# Shutdown_2019_v1_1_Faults.net
KiCad netlist of a schematic drawn in Altium Designer
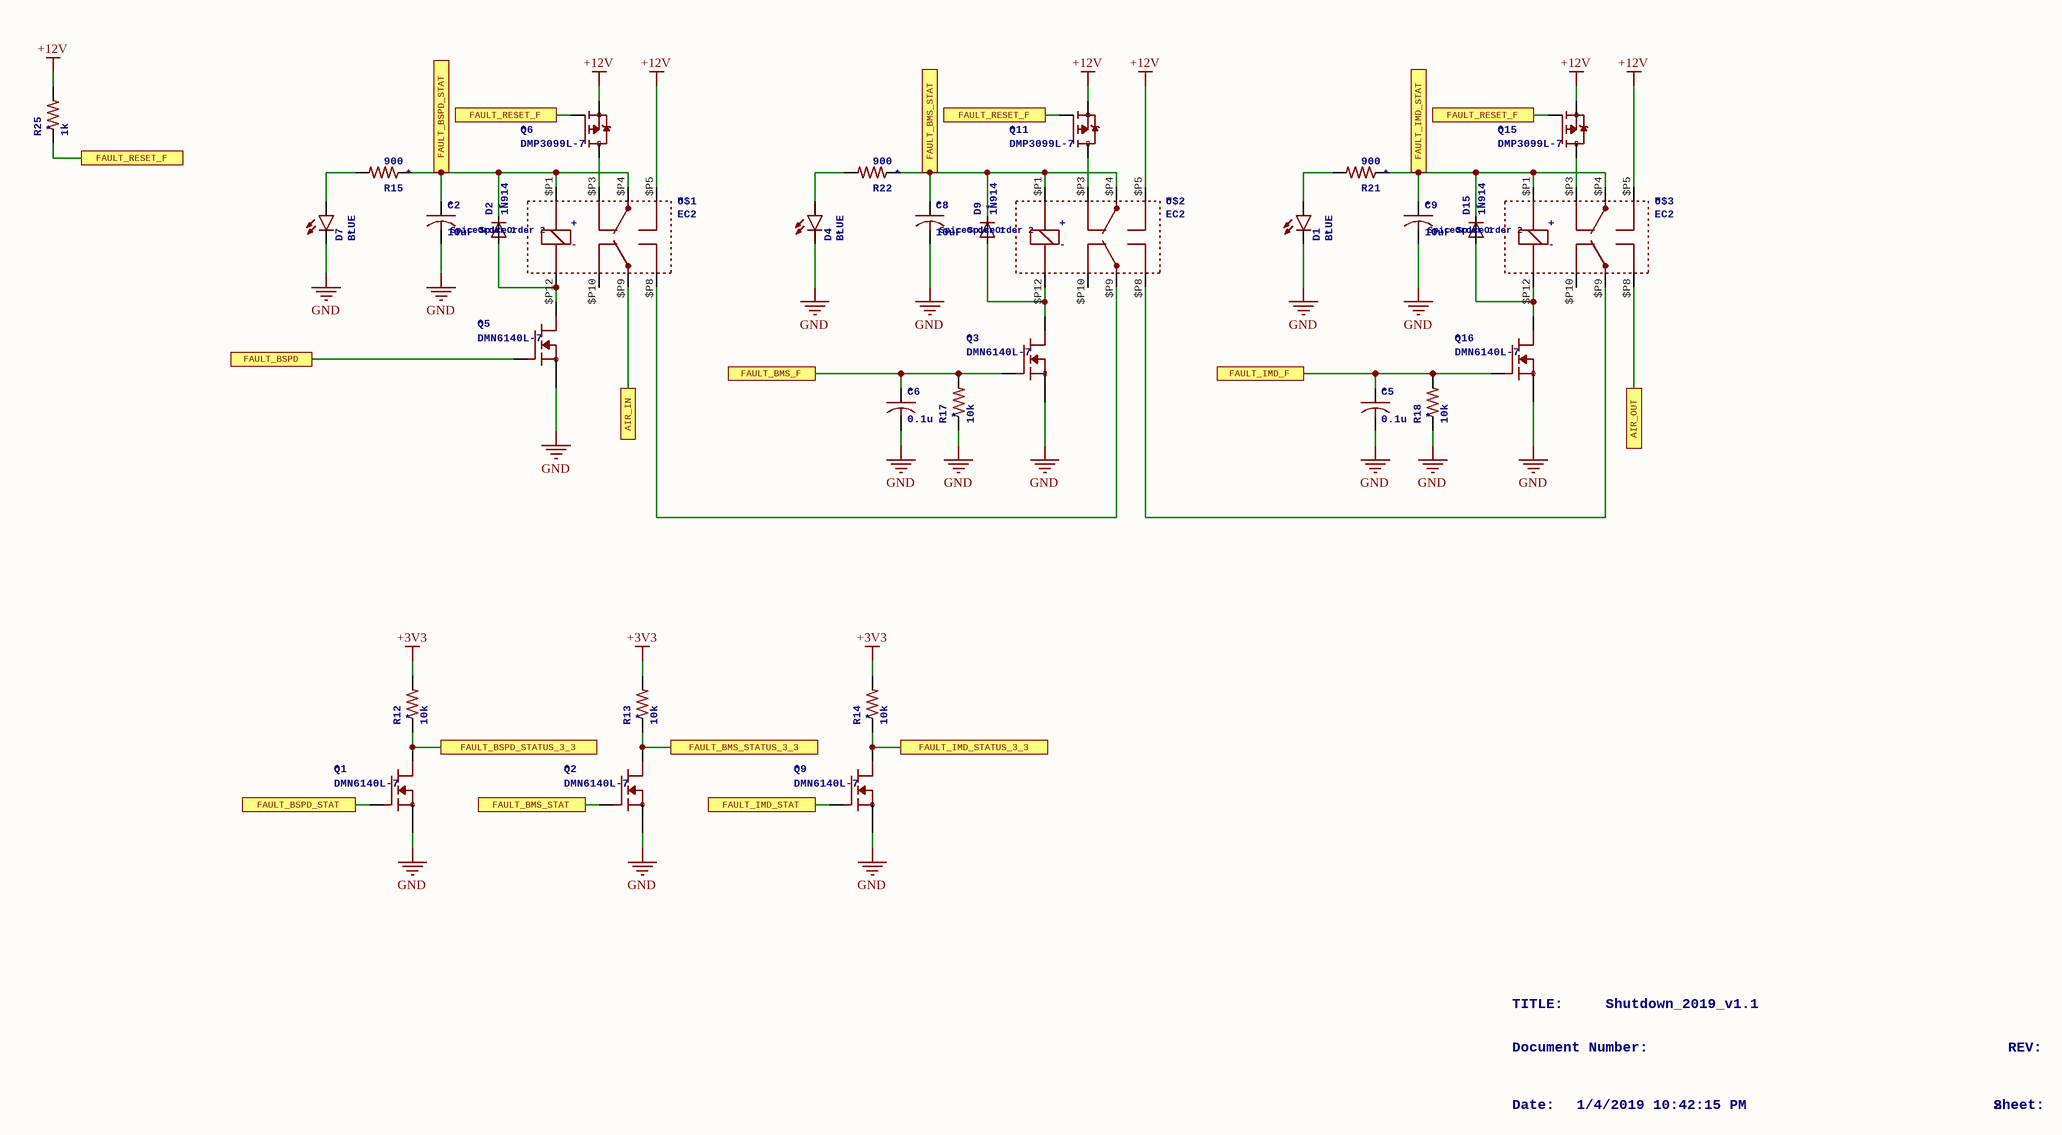
[diagram p0: Shutdown_2019_v1.1_Faults.SchDoc]

(export (version "E")
  (design (tool "Eeschema 10.0.6"))
  (components
    (comp (ref "C2")
      (value "10uF")
      (footprint "C0805")
      (description "CAPACITOR, American symbol")
      (fields (field (name "NAME") "*"))
      (libsource (lib "rcl") (part "C-USC0805"))
    )
    (comp (ref "C5")
      (value "0.1u")
      (footprint "C0603")
      (description "CAPACITOR, American symbol")
      (fields (field (name "NAME") "*"))
      (libsource (lib "resistor") (part "C-USC0603"))
    )
    (comp (ref "C6")
      (value "0.1u")
      (footprint "C0603")
      (description "CAPACITOR, American symbol")
      (fields (field (name "NAME") "*"))
      (libsource (lib "resistor") (part "C-USC0603"))
    )
    (comp (ref "C8")
      (value "10uF")
      (footprint "C0805")
      (description "CAPACITOR, American symbol")
      (fields (field (name "NAME") "*"))
      (libsource (lib "rcl") (part "C-USC0805"))
    )
    (comp (ref "C9")
      (value "10uF")
      (footprint "C0805")
      (description "CAPACITOR, American symbol")
      (fields (field (name "NAME") "*"))
      (libsource (lib "rcl") (part "C-USC0805"))
    )
    (comp (ref "D1")
      (value "BLUE")
      (footprint "LED-0603")
      (fields (field (name "NAME") "*"))
      (libsource (lib "SparkFun-LED") (part "LED-BLUE0603"))
    )
    (comp (ref "D2")
      (value "1N914")
      (footprint "SOD323-F")
      (fields
        (field (name "NAME") "*")
        (field (name "SPICEORDER1") "SpiceOrder 1")
        (field (name "SPICEORDER2") "SpiceOrder 2")
      )
      (libsource (lib "Diodes") (part "1N914"))
    )
    (comp (ref "D4")
      (value "BLUE")
      (footprint "LED-0603")
      (fields (field (name "NAME") "*"))
      (libsource (lib "SparkFun-LED") (part "LED-BLUE0603"))
    )
    (comp (ref "D7")
      (value "BLUE")
      (footprint "LED-0603")
      (fields (field (name "NAME") "*"))
      (libsource (lib "SparkFun-LED") (part "LED-BLUE0603"))
    )
    (comp (ref "D9")
      (value "1N914")
      (footprint "SOD323-F")
      (fields
        (field (name "NAME") "*")
        (field (name "SPICEORDER1") "SpiceOrder 1")
        (field (name "SPICEORDER2") "SpiceOrder 2")
      )
      (libsource (lib "Diodes") (part "1N914"))
    )
    (comp (ref "D15")
      (value "1N914")
      (footprint "SOD323-F")
      (fields
        (field (name "NAME") "*")
        (field (name "SPICEORDER1") "SpiceOrder 1")
        (field (name "SPICEORDER2") "SpiceOrder 2")
      )
      (libsource (lib "Diodes") (part "1N914"))
    )
    (comp (ref "Q1")
      (value "DMN6140L-7")
      (footprint "SOT23")
      (description "DMN6140L-7 Vgs(th) = 3V, Rds(on) = 140mOhm, Vds(max) = 60V")
      (fields (field (name "NAME") "*"))
      (libsource (lib "TRANS") (part "DMN6140L-7"))
    )
    (comp (ref "Q2")
      (value "DMN6140L-7")
      (footprint "SOT23")
      (description "DMN6140L-7 Vgs(th) = 3V, Rds(on) = 140mOhm, Vds(max) = 60V")
      (fields (field (name "NAME") "*"))
      (libsource (lib "TRANS") (part "DMN6140L-7"))
    )
    (comp (ref "Q3")
      (value "DMN6140L-7")
      (footprint "SOT23")
      (description "DMN6140L-7 Vgs(th) = 3V, Rds(on) = 140mOhm, Vds(max) = 60V")
      (fields (field (name "NAME") "*"))
      (libsource (lib "TRANS") (part "DMN6140L-7"))
    )
    (comp (ref "Q5")
      (value "DMN6140L-7")
      (footprint "SOT23")
      (description "DMN6140L-7 Vgs(th) = 3V, Rds(on) = 140mOhm, Vds(max) = 60V")
      (fields (field (name "NAME") "*"))
      (libsource (lib "TRANS") (part "DMN6140L-7"))
    )
    (comp (ref "Q6")
      (value "DMP3099L-7")
      (footprint "SOT23")
      (description "DMP3099L-7  P-Channel Vgs(th) = 2.1V, Rds(on) = 64 mohm, Vds(max) = 30V")
      (fields (field (name "NAME") "*"))
      (libsource (lib "TRANS") (part "DMP3099L-7"))
    )
    (comp (ref "Q9")
      (value "DMN6140L-7")
      (footprint "SOT23")
      (description "DMN6140L-7 Vgs(th) = 3V, Rds(on) = 140mOhm, Vds(max) = 60V")
      (fields (field (name "NAME") "*"))
      (libsource (lib "TRANS") (part "DMN6140L-7"))
    )
    (comp (ref "Q11")
      (value "DMP3099L-7")
      (footprint "SOT23")
      (description "DMP3099L-7  P-Channel Vgs(th) = 2.1V, Rds(on) = 64 mohm, Vds(max) = 30V")
      (fields (field (name "NAME") "*"))
      (libsource (lib "TRANS") (part "DMP3099L-7"))
    )
    (comp (ref "Q15")
      (value "DMP3099L-7")
      (footprint "SOT23")
      (description "DMP3099L-7  P-Channel Vgs(th) = 2.1V, Rds(on) = 64 mohm, Vds(max) = 30V")
      (fields (field (name "NAME") "*"))
      (libsource (lib "TRANS") (part "DMP3099L-7"))
    )
    (comp (ref "Q16")
      (value "DMN6140L-7")
      (footprint "SOT23")
      (description "DMN6140L-7 Vgs(th) = 3V, Rds(on) = 140mOhm, Vds(max) = 60V")
      (fields (field (name "NAME") "*"))
      (libsource (lib "TRANS") (part "DMN6140L-7"))
    )
    (comp (ref "R12")
      (value "10k")
      (footprint "R0603")
      (description "RESISTOR, American symbol")
      (fields (field (name "NAME") "*"))
      (libsource (lib "resistor") (part "R-US_R0603"))
    )
    (comp (ref "R13")
      (value "10k")
      (footprint "R0603")
      (description "RESISTOR, American symbol")
      (fields (field (name "NAME") "*"))
      (libsource (lib "resistor") (part "R-US_R0603"))
    )
    (comp (ref "R14")
      (value "10k")
      (footprint "R0603")
      (description "RESISTOR, American symbol")
      (fields (field (name "NAME") "*"))
      (libsource (lib "resistor") (part "R-US_R0603"))
    )
    (comp (ref "R15")
      (value "900")
      (footprint "R0603")
      (description "RESISTOR, American symbol")
      (fields (field (name "NAME") "*"))
      (libsource (lib "resistor") (part "R-US_R0603"))
    )
    (comp (ref "R17")
      (value "10k")
      (footprint "R0603")
      (description "RESISTOR, American symbol")
      (fields (field (name "NAME") "*"))
      (libsource (lib "resistor") (part "R-US_R0603"))
    )
    (comp (ref "R18")
      (value "10k")
      (footprint "R0603")
      (description "RESISTOR, American symbol")
      (fields (field (name "NAME") "*"))
      (libsource (lib "resistor") (part "R-US_R0603"))
    )
    (comp (ref "R21")
      (value "900")
      (footprint "R0603")
      (description "RESISTOR, American symbol")
      (fields (field (name "NAME") "*"))
      (libsource (lib "resistor") (part "R-US_R0603"))
    )
    (comp (ref "R22")
      (value "900")
      (footprint "R0603")
      (description "RESISTOR, American symbol")
      (fields (field (name "NAME") "*"))
      (libsource (lib "resistor") (part "R-US_R0603"))
    )
    (comp (ref "R25")
      (value "1k")
      (footprint "R0603")
      (description "RESISTOR, American symbol")
      (fields (field (name "NAME") "*"))
      (libsource (lib "resistor") (part "R-US_R0603"))
    )
    (comp (ref "U$1")
      (value "EC2")
      (footprint "DPDT_2.54")
      (description "KEMET EC2 DPDT General Purpose 2A Relay. 12V coil voltage.Datasheet Digikey")
      (fields (field (name "NAME") "*") (field (name "+") "+") (field (name "-") "-"))
      (libsource (lib "KEMET") (part "EC2"))
    )
    (comp (ref "U$2")
      (value "EC2")
      (footprint "DPDT_2.54")
      (description "KEMET EC2 DPDT General Purpose 2A Relay. 12V coil voltage.Datasheet Digikey")
      (fields (field (name "NAME") "*") (field (name "+") "+") (field (name "-") "-"))
      (libsource (lib "KEMET") (part "EC2"))
    )
    (comp (ref "U$3")
      (value "EC2")
      (footprint "DPDT_2.54")
      (description "KEMET EC2 DPDT General Purpose 2A Relay. 12V coil voltage.Datasheet Digikey")
      (fields (field (name "NAME") "*") (field (name "+") "+") (field (name "-") "-"))
      (libsource (lib "KEMET") (part "EC2"))
    )
  )
  (nets
    (net (code "1") (name "+3V3") (class "Default")
      (node (ref "R12") (pin "2") (pinfunction "2_2") (pintype "passive"))
      (node (ref "R13") (pin "2") (pinfunction "2_2") (pintype "passive"))
      (node (ref "R14") (pin "2") (pinfunction "2_2") (pintype "passive"))
    )
    (net (code "2") (name "+12V") (class "Default")
      (node (ref "Q11") (pin "2") (pinfunction "S_2") (pintype "passive"))
      (node (ref "Q15") (pin "2") (pinfunction "S_2") (pintype "passive"))
      (node (ref "Q6") (pin "2") (pinfunction "S_2") (pintype "passive"))
      (node (ref "R25") (pin "2") (pinfunction "2_2") (pintype "passive"))
      (node (ref "U$1") (pin "$P5") (pinfunction "$P5_$P5") (pintype "passive"))
      (node (ref "U$2") (pin "$P5") (pinfunction "$P5_$P5") (pintype "passive"))
      (node (ref "U$3") (pin "$P5") (pinfunction "$P5_$P5") (pintype "passive"))
    )
    (net (code "3") (name "/AIR_IN") (class "Default")
      (node (ref "U$1") (pin "$P9") (pinfunction "$P9_$P9") (pintype "passive"))
    )
    (net (code "4") (name "/AIR_OUT") (class "Default")
      (node (ref "U$3") (pin "$P8") (pinfunction "$P8_$P8") (pintype "passive"))
    )
    (net (code "5") (name "/FAULT_BMS_F") (class "Default")
      (node (ref "C6") (pin "1") (pinfunction "1_1") (pintype "passive"))
      (node (ref "Q3") (pin "1") (pinfunction "G_1") (pintype "passive"))
      (node (ref "R17") (pin "2") (pinfunction "2_2") (pintype "passive"))
    )
    (net (code "6") (name "/FAULT_BMS_STAT") (class "Default")
      (node (ref "C8") (pin "1") (pinfunction "1_1") (pintype "passive"))
      (node (ref "D9") (pin "C") (pinfunction "C_C") (pintype "passive"))
      (node (ref "Q2") (pin "1") (pinfunction "G_1") (pintype "passive"))
      (node (ref "R22") (pin "1") (pinfunction "1_1") (pintype "passive"))
      (node (ref "U$2") (pin "$P1") (pinfunction "$P1_$P1") (pintype "passive"))
      (node (ref "U$2") (pin "$P4") (pinfunction "$P4_$P4") (pintype "passive"))
    )
    (net (code "7") (name "/FAULT_BMS_STATUS_3_3") (class "Default")
      (node (ref "Q2") (pin "3") (pinfunction "D_3") (pintype "passive"))
      (node (ref "R13") (pin "1") (pinfunction "1_1") (pintype "passive"))
    )
    (net (code "8") (name "/FAULT_BSPD") (class "Default")
      (node (ref "Q5") (pin "1") (pinfunction "G_1") (pintype "passive"))
    )
    (net (code "9") (name "/FAULT_BSPD_STAT") (class "Default")
      (node (ref "C2") (pin "1") (pinfunction "1_1") (pintype "passive"))
      (node (ref "D2") (pin "C") (pinfunction "C_C") (pintype "passive"))
      (node (ref "Q1") (pin "1") (pinfunction "G_1") (pintype "passive"))
      (node (ref "R15") (pin "1") (pinfunction "1_1") (pintype "passive"))
      (node (ref "U$1") (pin "$P1") (pinfunction "$P1_$P1") (pintype "passive"))
      (node (ref "U$1") (pin "$P4") (pinfunction "$P4_$P4") (pintype "passive"))
    )
    (net (code "10") (name "/FAULT_BSPD_STATUS_3_3") (class "Default")
      (node (ref "Q1") (pin "3") (pinfunction "D_3") (pintype "passive"))
      (node (ref "R12") (pin "1") (pinfunction "1_1") (pintype "passive"))
    )
    (net (code "11") (name "/FAULT_IMD_F") (class "Default")
      (node (ref "C5") (pin "1") (pinfunction "1_1") (pintype "passive"))
      (node (ref "Q16") (pin "1") (pinfunction "G_1") (pintype "passive"))
      (node (ref "R18") (pin "2") (pinfunction "2_2") (pintype "passive"))
    )
    (net (code "12") (name "/FAULT_IMD_STAT") (class "Default")
      (node (ref "C9") (pin "1") (pinfunction "1_1") (pintype "passive"))
      (node (ref "D15") (pin "C") (pinfunction "C_C") (pintype "passive"))
      (node (ref "Q9") (pin "1") (pinfunction "G_1") (pintype "passive"))
      (node (ref "R21") (pin "1") (pinfunction "1_1") (pintype "passive"))
      (node (ref "U$3") (pin "$P1") (pinfunction "$P1_$P1") (pintype "passive"))
      (node (ref "U$3") (pin "$P4") (pinfunction "$P4_$P4") (pintype "passive"))
    )
    (net (code "13") (name "/FAULT_IMD_STATUS_3_3") (class "Default")
      (node (ref "Q9") (pin "3") (pinfunction "D_3") (pintype "passive"))
      (node (ref "R14") (pin "1") (pinfunction "1_1") (pintype "passive"))
    )
    (net (code "14") (name "/FAULT_RESET_F") (class "Default")
      (node (ref "Q11") (pin "1") (pinfunction "G_1") (pintype "passive"))
      (node (ref "Q15") (pin "1") (pinfunction "G_1") (pintype "passive"))
      (node (ref "Q6") (pin "1") (pinfunction "G_1") (pintype "passive"))
      (node (ref "R25") (pin "1") (pinfunction "1_1") (pintype "passive"))
    )
    (net (code "15") (name "GND") (class "Default")
      (node (ref "C2") (pin "2") (pinfunction "2_2") (pintype "passive"))
      (node (ref "C5") (pin "2") (pinfunction "2_2") (pintype "passive"))
      (node (ref "C6") (pin "2") (pinfunction "2_2") (pintype "passive"))
      (node (ref "C8") (pin "2") (pinfunction "2_2") (pintype "passive"))
      (node (ref "C9") (pin "2") (pinfunction "2_2") (pintype "passive"))
      (node (ref "D1") (pin "C") (pinfunction "C_C") (pintype "passive"))
      (node (ref "D4") (pin "C") (pinfunction "C_C") (pintype "passive"))
      (node (ref "D7") (pin "C") (pinfunction "C_C") (pintype "passive"))
      (node (ref "Q1") (pin "2") (pinfunction "S_2") (pintype "passive"))
      (node (ref "Q16") (pin "2") (pinfunction "S_2") (pintype "passive"))
      (node (ref "Q2") (pin "2") (pinfunction "S_2") (pintype "passive"))
      (node (ref "Q3") (pin "2") (pinfunction "S_2") (pintype "passive"))
      (node (ref "Q5") (pin "2") (pinfunction "S_2") (pintype "passive"))
      (node (ref "Q9") (pin "2") (pinfunction "S_2") (pintype "passive"))
      (node (ref "R17") (pin "1") (pinfunction "1_1") (pintype "passive"))
      (node (ref "R18") (pin "1") (pinfunction "1_1") (pintype "passive"))
    )
    (net (code "16") (name "Net-(D1-PadA)") (class "Default")
      (node (ref "D1") (pin "A") (pinfunction "A_A") (pintype "passive"))
      (node (ref "R21") (pin "2") (pinfunction "2_2") (pintype "passive"))
    )
    (net (code "17") (name "Net-(D4-PadA)") (class "Default")
      (node (ref "D4") (pin "A") (pinfunction "A_A") (pintype "passive"))
      (node (ref "R22") (pin "2") (pinfunction "2_2") (pintype "passive"))
    )
    (net (code "18") (name "Net-(D7-PadA)") (class "Default")
      (node (ref "D7") (pin "A") (pinfunction "A_A") (pintype "passive"))
      (node (ref "R15") (pin "2") (pinfunction "2_2") (pintype "passive"))
    )
    (net (code "19") (name "Net-(Q3-D)") (class "Default")
      (node (ref "D9") (pin "A") (pinfunction "A_A") (pintype "passive"))
      (node (ref "Q3") (pin "3") (pinfunction "D_3") (pintype "passive"))
      (node (ref "U$2") (pin "$P12") (pinfunction "$P12_$P12") (pintype "passive"))
    )
    (net (code "20") (name "Net-(Q5-D)") (class "Default")
      (node (ref "D2") (pin "A") (pinfunction "A_A") (pintype "passive"))
      (node (ref "Q5") (pin "3") (pinfunction "D_3") (pintype "passive"))
      (node (ref "U$1") (pin "$P12") (pinfunction "$P12_$P12") (pintype "passive"))
    )
    (net (code "21") (name "Net-(Q6-D)") (class "Default")
      (node (ref "Q6") (pin "3") (pinfunction "D_3") (pintype "passive"))
      (node (ref "U$1") (pin "$P3") (pinfunction "$P3_$P3") (pintype "passive"))
    )
    (net (code "22") (name "Net-(Q11-D)") (class "Default")
      (node (ref "Q11") (pin "3") (pinfunction "D_3") (pintype "passive"))
      (node (ref "U$2") (pin "$P3") (pinfunction "$P3_$P3") (pintype "passive"))
    )
    (net (code "23") (name "Net-(Q15-D)") (class "Default")
      (node (ref "Q15") (pin "3") (pinfunction "D_3") (pintype "passive"))
      (node (ref "U$3") (pin "$P3") (pinfunction "$P3_$P3") (pintype "passive"))
    )
    (net (code "24") (name "Net-(Q16-D)") (class "Default")
      (node (ref "D15") (pin "A") (pinfunction "A_A") (pintype "passive"))
      (node (ref "Q16") (pin "3") (pinfunction "D_3") (pintype "passive"))
      (node (ref "U$3") (pin "$P12") (pinfunction "$P12_$P12") (pintype "passive"))
    )
    (net (code "25") (name "Net-(U$1-Pad$P8)") (class "Default")
      (node (ref "U$1") (pin "$P8") (pinfunction "$P8_$P8") (pintype "passive"))
      (node (ref "U$2") (pin "$P9") (pinfunction "$P9_$P9") (pintype "passive"))
    )
    (net (code "26") (name "Net-(U$2-Pad$P8)") (class "Default")
      (node (ref "U$2") (pin "$P8") (pinfunction "$P8_$P8") (pintype "passive"))
      (node (ref "U$3") (pin "$P9") (pinfunction "$P9_$P9") (pintype "passive"))
    )
    (net (code "27") (name "unconnected-(U$1-Pad$P10)") (class "Default")
      (node (ref "U$1") (pin "$P10") (pinfunction "$P10_$P10") (pintype "passive"))
    )
    (net (code "28") (name "unconnected-(U$2-Pad$P10)") (class "Default")
      (node (ref "U$2") (pin "$P10") (pinfunction "$P10_$P10") (pintype "passive"))
    )
    (net (code "29") (name "unconnected-(U$3-Pad$P10)") (class "Default")
      (node (ref "U$3") (pin "$P10") (pinfunction "$P10_$P10") (pintype "passive"))
    )
  )
)
